# tqfp-sandwich-rf.net
KiCad netlist of a schematic drawn in EAGLE
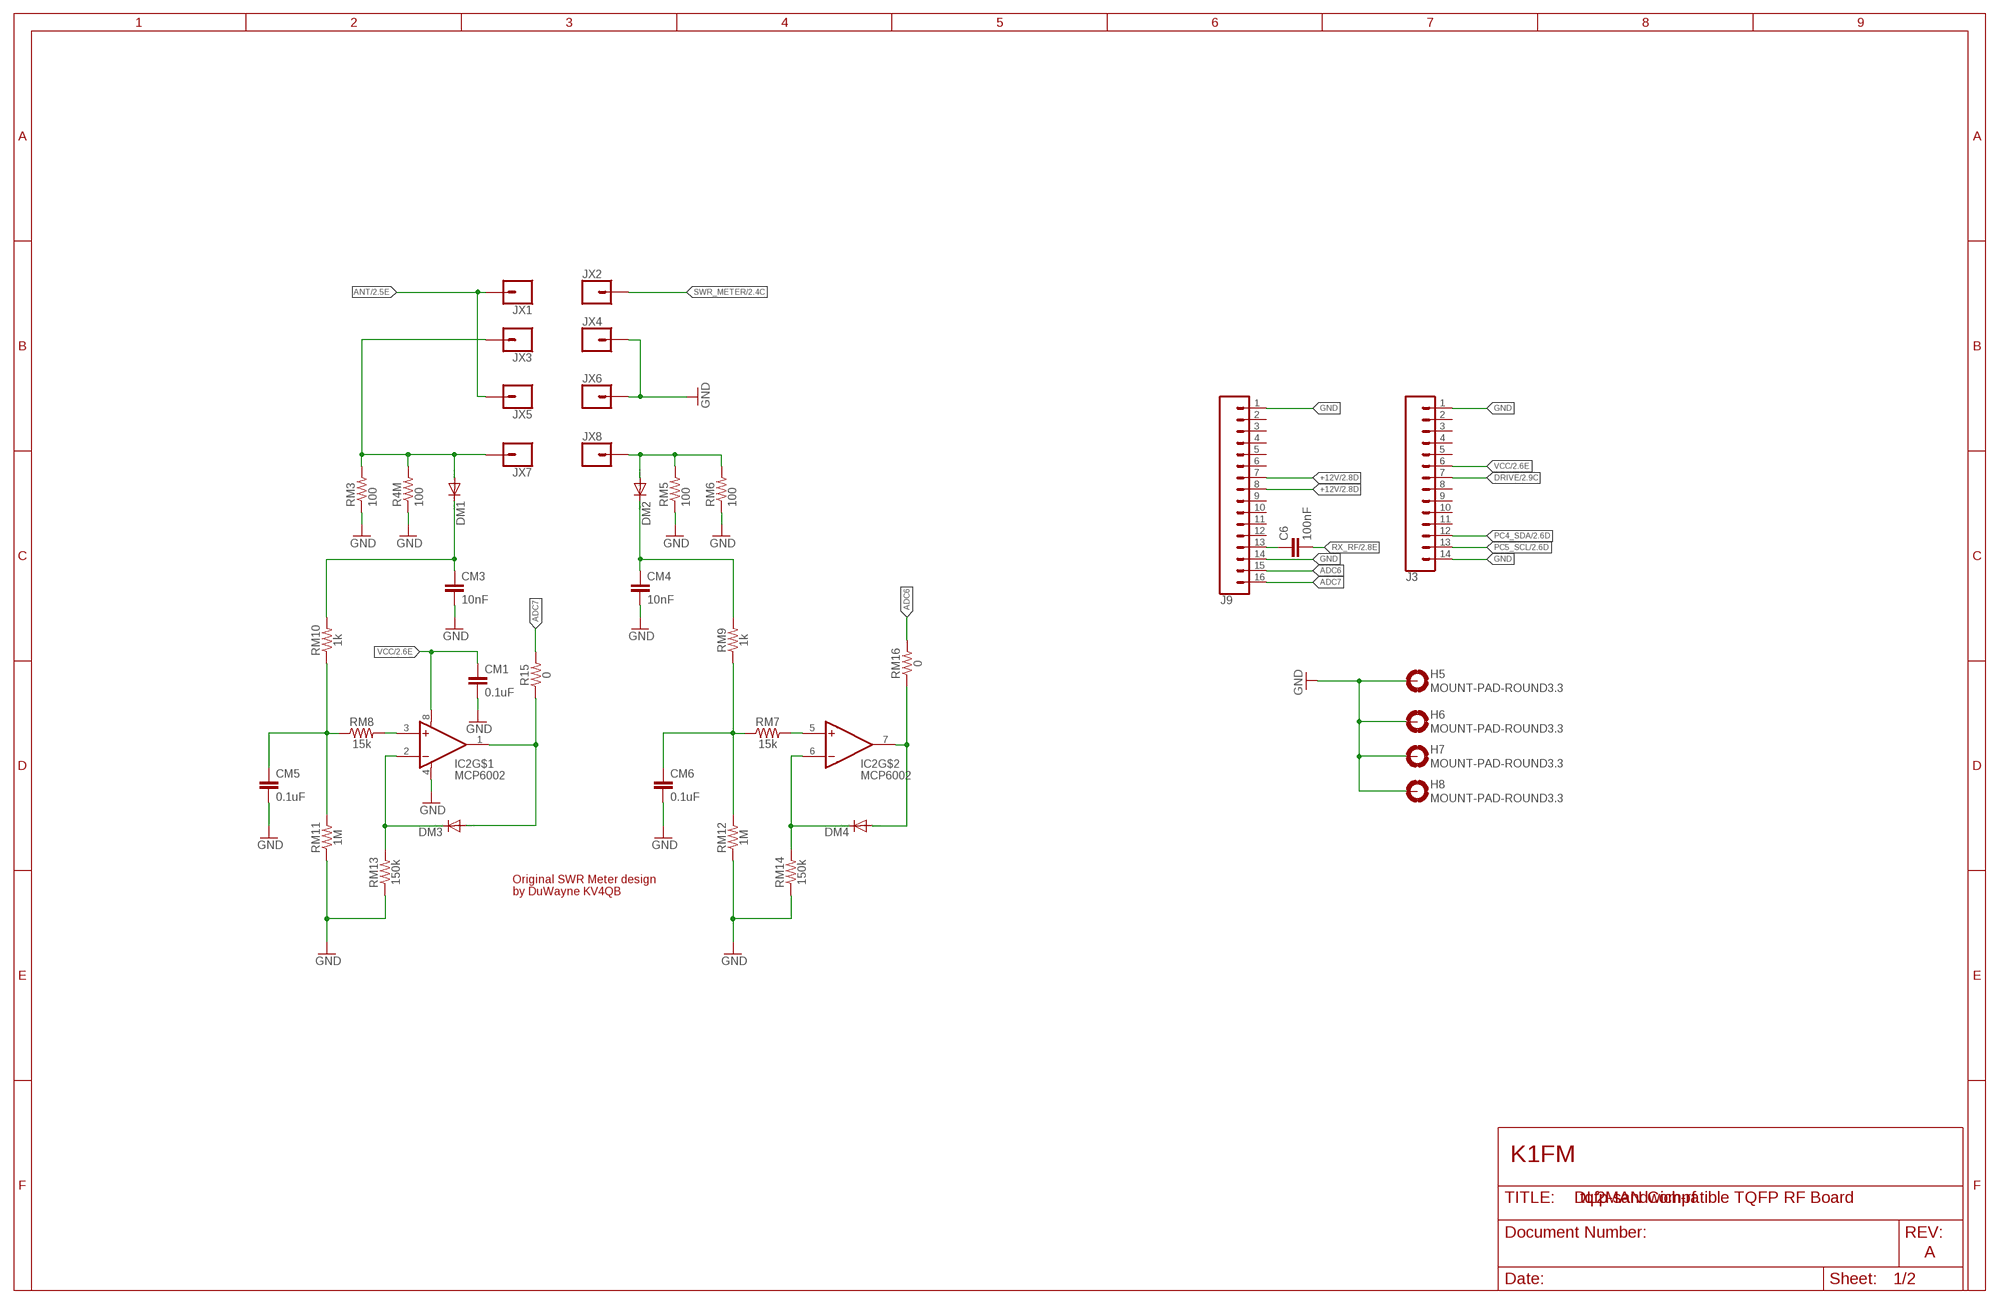
[diagram p0: schematic, sheet 1]
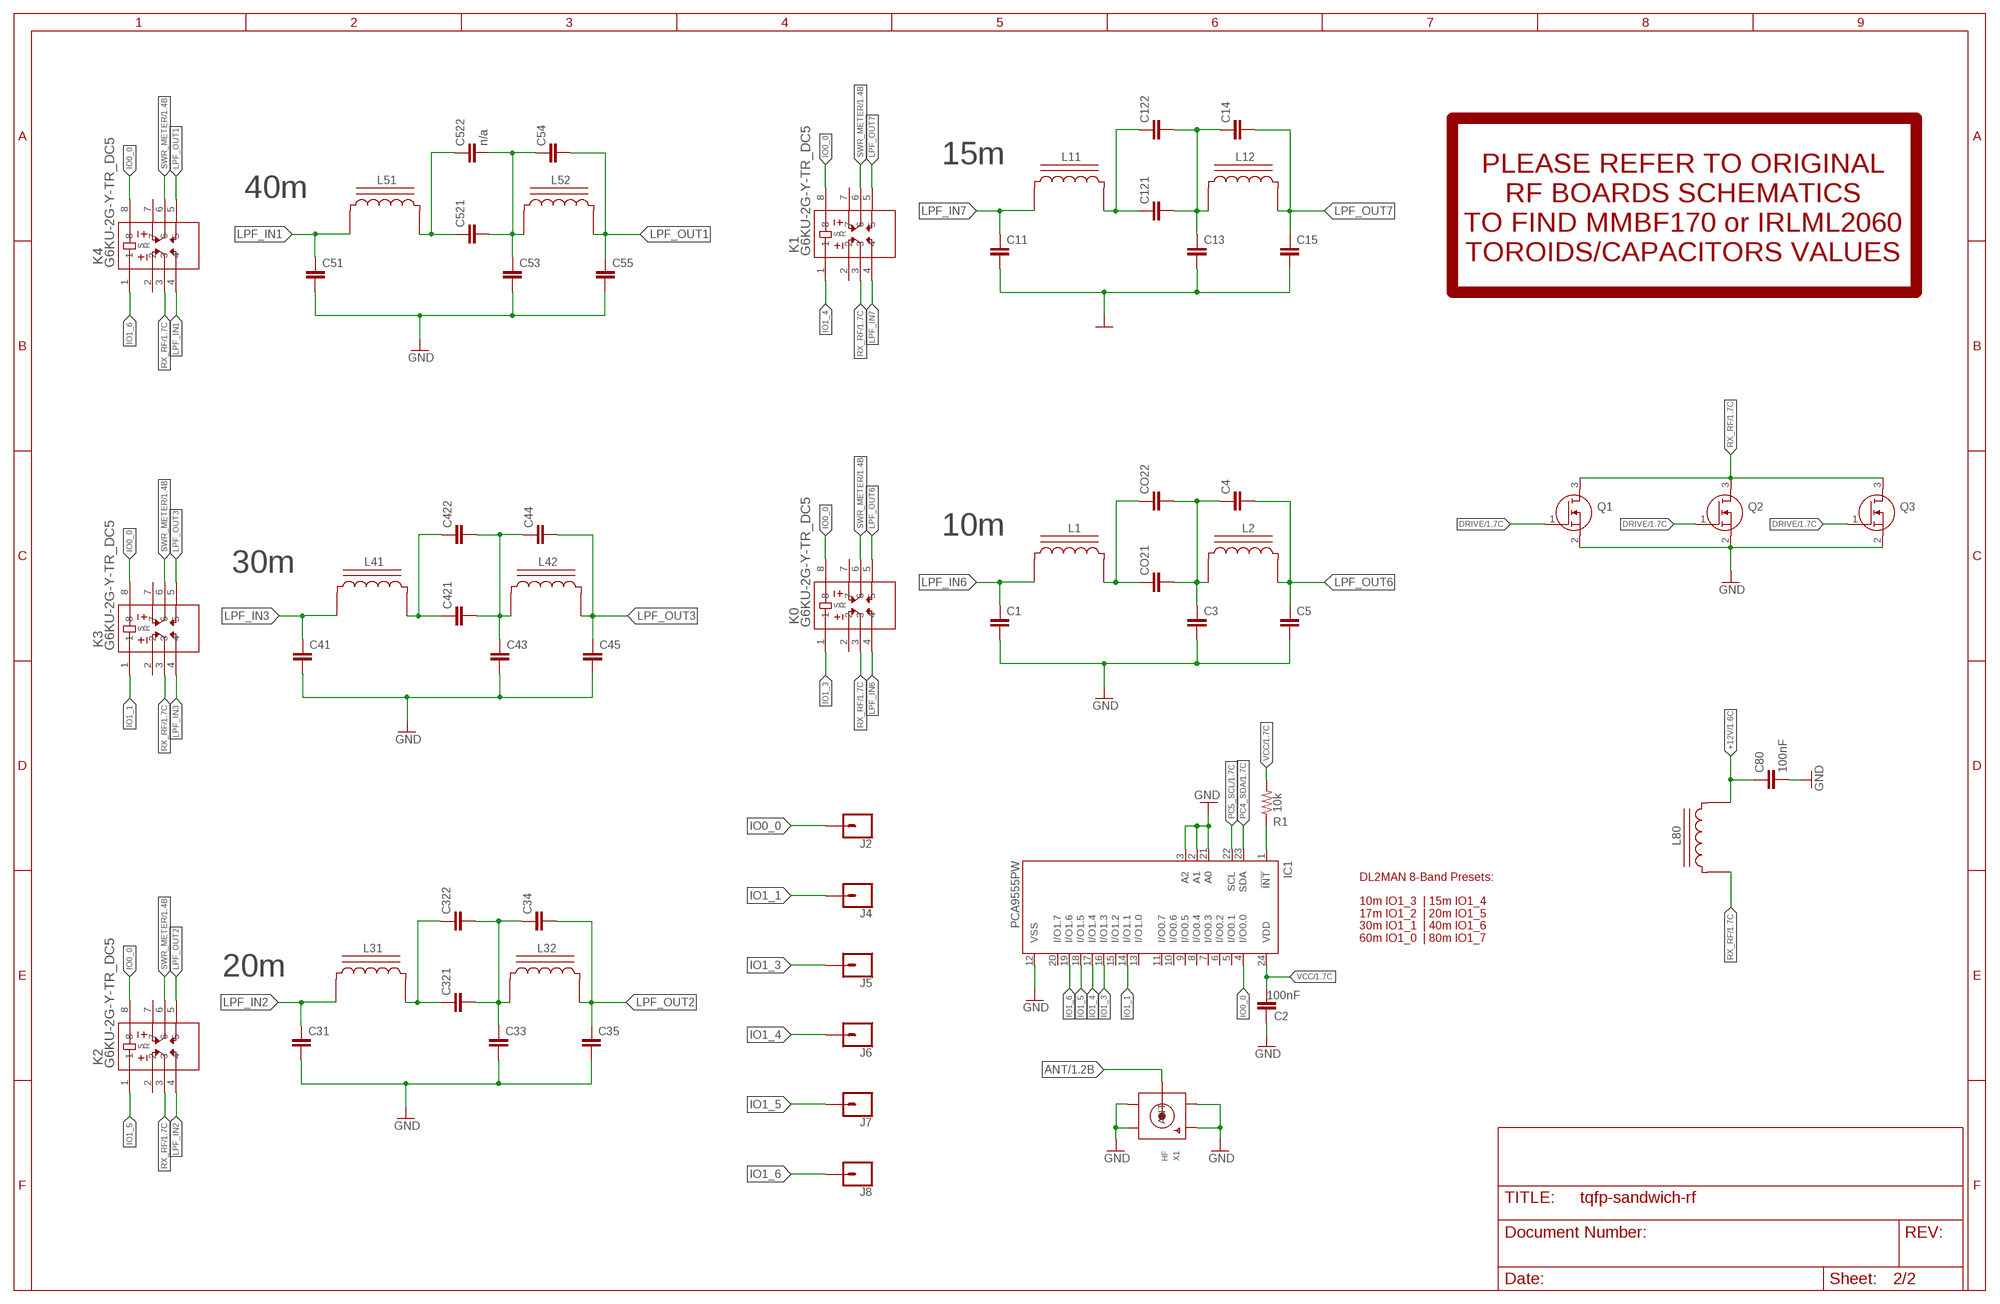
[diagram p1: schematic, sheet 2]

(export (version "E")
  (design (tool "Eeschema 10.0.6"))
  (components
    (comp (ref "C1")
      (value "82pF")
      (footprint "eagle-import:RESC0805_L")
      (libsource (lib "eagle-import") (part "CAPACITOR_0805_L"))
    )
    (comp (ref "C2")
      (value "100nF")
      (footprint "eagle-import:RESC0805_L")
      (libsource (lib "eagle-import") (part "CAPACITOR_0805_L"))
    )
    (comp (ref "C3")
      (value "240pF")
      (footprint "eagle-import:RESC0805_L")
      (libsource (lib "eagle-import") (part "CAPACITOR_0805_L"))
    )
    (comp (ref "C4")
      (value "82pF")
      (footprint "eagle-import:RESC0805_L")
      (libsource (lib "eagle-import") (part "CAPACITOR_0805_L"))
    )
    (comp (ref "C5")
      (value "220pF")
      (footprint "eagle-import:RESC0805_L")
      (libsource (lib "eagle-import") (part "CAPACITOR_0805_L"))
    )
    (comp (ref "C11")
      (value "100pF")
      (footprint "eagle-import:RESC0805_L")
      (libsource (lib "eagle-import") (part "CAPACITOR_0805_L"))
    )
    (comp (ref "C13")
      (value "330pF")
      (footprint "eagle-import:RESC0805_L")
      (libsource (lib "eagle-import") (part "CAPACITOR_0805_L"))
    )
    (comp (ref "C14")
      (value "100pF")
      (footprint "eagle-import:RESC0805_L")
      (libsource (lib "eagle-import") (part "CAPACITOR_0805_L"))
    )
    (comp (ref "C15")
      (value "300pF")
      (footprint "eagle-import:RESC0805_L")
      (libsource (lib "eagle-import") (part "CAPACITOR_0805_L"))
    )
    (comp (ref "C31")
      (value "180pF")
      (footprint "eagle-import:RESC0805_L")
      (libsource (lib "eagle-import") (part "CAPACITOR_0805_L"))
    )
    (comp (ref "C33")
      (value "470pF")
      (footprint "eagle-import:RESC0805_L")
      (libsource (lib "eagle-import") (part "CAPACITOR_0805_L"))
    )
    (comp (ref "C34")
      (value "150pF")
      (footprint "eagle-import:RESC0805_L")
      (libsource (lib "eagle-import") (part "CAPACITOR_0805_L"))
    )
    (comp (ref "C35")
      (value "430pF")
      (footprint "eagle-import:RESC0805_L")
      (libsource (lib "eagle-import") (part "CAPACITOR_0805_L"))
    )
    (comp (ref "C41")
      (value "220pF")
      (footprint "eagle-import:RESC0805_L")
      (libsource (lib "eagle-import") (part "CAPACITOR_0805_L"))
    )
    (comp (ref "C43")
      (value "680pF")
      (footprint "eagle-import:RESC0805_L")
      (libsource (lib "eagle-import") (part "CAPACITOR_0805_L"))
    )
    (comp (ref "C44")
      (value "220pF")
      (footprint "eagle-import:RESC0805_L")
      (libsource (lib "eagle-import") (part "CAPACITOR_0805_L"))
    )
    (comp (ref "C45")
      (value "620pF")
      (footprint "eagle-import:RESC0805_L")
      (libsource (lib "eagle-import") (part "CAPACITOR_0805_L"))
    )
    (comp (ref "C51")
      (value "360pF")
      (footprint "eagle-import:RESC0805_L")
      (libsource (lib "eagle-import") (part "CAPACITOR_0805_L"))
    )
    (comp (ref "C53")
      (value "620pF+330pF")
      (footprint "eagle-import:RESC0805_L")
      (libsource (lib "eagle-import") (part "CAPACITOR_0805_L"))
    )
    (comp (ref "C54")
      (value "330pF")
      (footprint "eagle-import:RESC0805_L")
      (libsource (lib "eagle-import") (part "CAPACITOR_0805_L"))
    )
    (comp (ref "C55")
      (value "470pF+430pF")
      (footprint "eagle-import:RESC0805_L")
      (libsource (lib "eagle-import") (part "CAPACITOR_0805_L"))
    )
    (comp (ref "C80")
      (value "100nF")
      (footprint "eagle-import:RESC0805_L")
      (libsource (lib "eagle-import") (part "CAPACITOR_0805_L"))
    )
    (comp (ref "C121")
      (value "15pF")
      (footprint "eagle-import:RESC0805_L")
      (libsource (lib "eagle-import") (part "CAPACITOR_0805_L"))
    )
    (comp (ref "C122")
      (value "330pF")
      (footprint "eagle-import:RESC0805_L")
      (libsource (lib "eagle-import") (part "CAPACITOR_0805_L"))
    )
    (comp (ref "C321")
      (value "220pF")
      (footprint "eagle-import:RESC0805_L")
      (libsource (lib "eagle-import") (part "CAPACITOR_0805_L"))
    )
    (comp (ref "C322")
      (value "300pF")
      (footprint "eagle-import:RESC0805_L")
      (libsource (lib "eagle-import") (part "CAPACITOR_0805_L"))
    )
    (comp (ref "C421")
      (value "100pF")
      (footprint "eagle-import:RESC0805_L")
      (libsource (lib "eagle-import") (part "CAPACITOR_0805_L"))
    )
    (comp (ref "C422")
      (value "620pF")
      (footprint "eagle-import:RESC0805_L")
      (libsource (lib "eagle-import") (part "CAPACITOR_0805_L"))
    )
    (comp (ref "C521")
      (value "1000pF")
      (footprint "eagle-import:RESC0805_L")
      (libsource (lib "eagle-import") (part "CAPACITOR_0805_L"))
    )
    (comp (ref "C522")
      (value "n/a")
      (footprint "eagle-import:RESC0805_L")
      (libsource (lib "eagle-import") (part "CAPACITOR_0805_L"))
    )
    (comp (ref "CO21")
      (value "56pF")
      (footprint "eagle-import:RESC0805_L")
      (libsource (lib "eagle-import") (part "CAPACITOR_0805_L"))
    )
    (comp (ref "CO22")
      (value "200pF")
      (footprint "eagle-import:RESC0805_L")
      (libsource (lib "eagle-import") (part "CAPACITOR_0805_L"))
    )
    (comp (ref "IC1")
      (value "PCA9555PW")
      (footprint "eagle-import:TSSOP24")
      (libsource (lib "eagle-import") (part "PCA9555PW"))
    )
    (comp (ref "J2")
      (value "CONN_01OFFSET")
      (footprint "eagle-import:1X01_OFFSET")
      (libsource (lib "eagle-import") (part "CONN_01OFFSET"))
    )
    (comp (ref "J4")
      (value "CONN_01OFFSET")
      (footprint "eagle-import:1X01_OFFSET")
      (libsource (lib "eagle-import") (part "CONN_01OFFSET"))
    )
    (comp (ref "J5")
      (value "CONN_01OFFSET")
      (footprint "eagle-import:1X01_OFFSET")
      (libsource (lib "eagle-import") (part "CONN_01OFFSET"))
    )
    (comp (ref "J6")
      (value "CONN_01OFFSET")
      (footprint "eagle-import:1X01_OFFSET")
      (libsource (lib "eagle-import") (part "CONN_01OFFSET"))
    )
    (comp (ref "J7")
      (value "CONN_01OFFSET")
      (footprint "eagle-import:1X01_OFFSET")
      (libsource (lib "eagle-import") (part "CONN_01OFFSET"))
    )
    (comp (ref "J8")
      (value "CONN_01OFFSET")
      (footprint "eagle-import:1X01_OFFSET")
      (libsource (lib "eagle-import") (part "CONN_01OFFSET"))
    )
    (comp (ref "K0")
      (value "G6KU-2G-Y-TR_DC5")
      (footprint "eagle-import:G6KU-2G-Y_DC3_OMR")
      (fields
        (field (name "MANUFACTURER_PART_NUMBER") "G6KU-2G-Y-TR DC5")
        (field (name "COPYRIGHT") "Copyright (C) 2018 Accelerated Designs. All rights reserved")
      )
      (libsource (lib "eagle-import") (part "G6KU-2G-Y-TR_DC5"))
    )
    (comp (ref "K1")
      (value "G6KU-2G-Y-TR_DC5")
      (footprint "eagle-import:G6KU-2G-Y_DC3_OMR")
      (fields
        (field (name "MANUFACTURER_PART_NUMBER") "G6KU-2G-Y-TR DC5")
        (field (name "COPYRIGHT") "Copyright (C) 2018 Accelerated Designs. All rights reserved")
      )
      (libsource (lib "eagle-import") (part "G6KU-2G-Y-TR_DC5"))
    )
    (comp (ref "K2")
      (value "G6KU-2G-Y-TR_DC5")
      (footprint "eagle-import:G6KU-2G-Y_DC3_OMR")
      (fields
        (field (name "MANUFACTURER_PART_NUMBER") "G6KU-2G-Y-TR DC5")
        (field (name "COPYRIGHT") "Copyright (C) 2018 Accelerated Designs. All rights reserved")
      )
      (libsource (lib "eagle-import") (part "G6KU-2G-Y-TR_DC5"))
    )
    (comp (ref "K3")
      (value "G6KU-2G-Y-TR_DC5")
      (footprint "eagle-import:G6KU-2G-Y_DC3_OMR")
      (fields
        (field (name "MANUFACTURER_PART_NUMBER") "G6KU-2G-Y-TR DC5")
        (field (name "COPYRIGHT") "Copyright (C) 2018 Accelerated Designs. All rights reserved")
      )
      (libsource (lib "eagle-import") (part "G6KU-2G-Y-TR_DC5"))
    )
    (comp (ref "K4")
      (value "G6KU-2G-Y-TR_DC5")
      (footprint "eagle-import:G6KU-2G-Y_DC3_OMR")
      (fields
        (field (name "MANUFACTURER_PART_NUMBER") "G6KU-2G-Y-TR DC5")
        (field (name "COPYRIGHT") "Copyright (C) 2018 Accelerated Designs. All rights reserved")
      )
      (libsource (lib "eagle-import") (part "G6KU-2G-Y-TR_DC5"))
    )
    (comp (ref "L1")
      (value "8T/T37-6")
      (footprint "eagle-import:T37_INDUCTOR")
      (libsource (lib "eagle-import") (part "T37_INDUCTOR"))
    )
    (comp (ref "L2")
      (value "5T/T37-6")
      (footprint "eagle-import:T37_INDUCTOR")
      (libsource (lib "eagle-import") (part "T37_INDUCTOR"))
    )
    (comp (ref "L11")
      (value "9T/T37-6")
      (footprint "eagle-import:T37_INDUCTOR")
      (libsource (lib "eagle-import") (part "T37_INDUCTOR"))
    )
    (comp (ref "L12")
      (value "6T/T37-6")
      (footprint "eagle-import:T37_INDUCTOR")
      (libsource (lib "eagle-import") (part "T37_INDUCTOR"))
    )
    (comp (ref "L31")
      (value "12T/T37-6")
      (footprint "eagle-import:T37_INDUCTOR")
      (libsource (lib "eagle-import") (part "T37_INDUCTOR"))
    )
    (comp (ref "L32")
      (value "8T/T37-2")
      (footprint "eagle-import:T37_INDUCTOR")
      (libsource (lib "eagle-import") (part "T37_INDUCTOR"))
    )
    (comp (ref "L41")
      (value "12T/T37-2")
      (footprint "eagle-import:T37_INDUCTOR")
      (libsource (lib "eagle-import") (part "T37_INDUCTOR"))
    )
    (comp (ref "L42")
      (value "8T/T37-2")
      (footprint "eagle-import:T37_INDUCTOR")
      (libsource (lib "eagle-import") (part "T37_INDUCTOR"))
    )
    (comp (ref "L51")
      (value "15T/T37-2")
      (footprint "eagle-import:T37_INDUCTOR")
      (libsource (lib "eagle-import") (part "T37_INDUCTOR"))
    )
    (comp (ref "L52")
      (value "9T/T37-2")
      (footprint "eagle-import:T37_INDUCTOR")
      (libsource (lib "eagle-import") (part "T37_INDUCTOR"))
    )
    (comp (ref "L80")
      (value "12T/FT37-43")
      (footprint "eagle-import:T37_INDUCTOR")
      (libsource (lib "eagle-import") (part "T37_INDUCTOR"))
    )
    (comp (ref "Q1")
      (value "MMBF170")
      (footprint "eagle-import:SOT96P237X111-3N")
      (fields (field (name "MOUSER_PART_NUMBER") "512-MMBF170"))
      (libsource (lib "eagle-import") (part "MMBF170"))
    )
    (comp (ref "Q2")
      (value "MMBF170")
      (footprint "eagle-import:SOT96P237X111-3N")
      (fields (field (name "MOUSER_PART_NUMBER") "512-MMBF170"))
      (libsource (lib "eagle-import") (part "MMBF170"))
    )
    (comp (ref "Q3")
      (value "MMBF170")
      (footprint "eagle-import:SOT96P237X111-3N")
      (fields (field (name "MOUSER_PART_NUMBER") "512-MMBF170"))
      (libsource (lib "eagle-import") (part "MMBF170"))
    )
    (comp (ref "R1")
      (value "10k")
      (footprint "eagle-import:0603")
      (libsource (lib "eagle-import") (part "10KOHM-0603-1/10W-1%"))
    )
    (comp (ref "X1")
      (value "HF")
      (footprint "eagle-import:SMA_EDGELAUNCH")
      (libsource (lib "eagle-import") (part "SMACONNECTOR_EDGE"))
    )
    (comp (ref "C6")
      (value "100nF")
      (footprint "eagle-import:RESC0805_L")
      (libsource (lib "eagle-import") (part "CAPACITOR_0805_L"))
    )
    (comp (ref "CM1")
      (value "0.1uF")
      (footprint "eagle-import:0603")
      (libsource (lib "eagle-import") (part "0.1UF-0603-100V-10%"))
    )
    (comp (ref "CM3")
      (value "10nF")
      (footprint "eagle-import:0603")
      (libsource (lib "eagle-import") (part "10NF-0603-50V-10%"))
    )
    (comp (ref "CM4")
      (value "10nF")
      (footprint "eagle-import:0603")
      (libsource (lib "eagle-import") (part "10NF-0603-50V-10%"))
    )
    (comp (ref "CM5")
      (value "0.1uF")
      (footprint "eagle-import:0603")
      (libsource (lib "eagle-import") (part "0.1UF-0603-100V-10%"))
    )
    (comp (ref "CM6")
      (value "0.1uF")
      (footprint "eagle-import:0603")
      (libsource (lib "eagle-import") (part "0.1UF-0603-100V-10%"))
    )
    (comp (ref "DM1")
      (value "1N60P")
      (footprint "eagle-import:DO35-10")
      (libsource (lib "eagle-import") (part "1N4148DO35-10"))
    )
    (comp (ref "DM2")
      (value "1N60P")
      (footprint "eagle-import:DO35-10")
      (libsource (lib "eagle-import") (part "1N4148DO35-10"))
    )
    (comp (ref "DM3")
      (value "1N60P")
      (footprint "eagle-import:DO35-10")
      (libsource (lib "eagle-import") (part "1N4148DO35-10"))
    )
    (comp (ref "DM4")
      (value "1N60P")
      (footprint "eagle-import:DO35-10")
      (libsource (lib "eagle-import") (part "1N4148DO35-10"))
    )
    (comp (ref "H5")
      (value "MOUNT-PAD-ROUND3.3")
      (footprint "eagle-import:3,3-PAD")
      (libsource (lib "eagle-import") (part "MOUNT-PAD-ROUND3.3"))
    )
    (comp (ref "H6")
      (value "MOUNT-PAD-ROUND3.3")
      (footprint "eagle-import:3,3-PAD")
      (libsource (lib "eagle-import") (part "MOUNT-PAD-ROUND3.3"))
    )
    (comp (ref "H7")
      (value "MOUNT-PAD-ROUND3.3")
      (footprint "eagle-import:3,3-PAD")
      (libsource (lib "eagle-import") (part "MOUNT-PAD-ROUND3.3"))
    )
    (comp (ref "H8")
      (value "MOUNT-PAD-ROUND3.3")
      (footprint "eagle-import:3,3-PAD")
      (libsource (lib "eagle-import") (part "MOUNT-PAD-ROUND3.3"))
    )
    (comp (ref "IC2")
      (value "MCP6002")
      (footprint "eagle-import:SOIC8")
      (libsource (lib "eagle-import") (part "MCP6293"))
    )
    (comp (ref "J3")
      (value "CONN_14")
      (footprint "eagle-import:1X14")
      (libsource (lib "eagle-import") (part "CONN_14"))
    )
    (comp (ref "J9")
      (value "CONN_16")
      (footprint "eagle-import:1X16")
      (libsource (lib "eagle-import") (part "CONN_16"))
    )
    (comp (ref "JX1")
      (value "CONN_01")
      (footprint "eagle-import:1X01")
      (libsource (lib "eagle-import") (part "CONN_01"))
    )
    (comp (ref "JX2")
      (value "CONN_01")
      (footprint "eagle-import:1X01")
      (libsource (lib "eagle-import") (part "CONN_01"))
    )
    (comp (ref "JX3")
      (value "CONN_01")
      (footprint "eagle-import:1X01")
      (libsource (lib "eagle-import") (part "CONN_01"))
    )
    (comp (ref "JX4")
      (value "CONN_01")
      (footprint "eagle-import:1X01")
      (libsource (lib "eagle-import") (part "CONN_01"))
    )
    (comp (ref "JX5")
      (value "CONN_01")
      (footprint "eagle-import:1X01")
      (libsource (lib "eagle-import") (part "CONN_01"))
    )
    (comp (ref "JX6")
      (value "CONN_01")
      (footprint "eagle-import:1X01")
      (libsource (lib "eagle-import") (part "CONN_01"))
    )
    (comp (ref "JX7")
      (value "CONN_01")
      (footprint "eagle-import:1X01")
      (libsource (lib "eagle-import") (part "CONN_01"))
    )
    (comp (ref "JX8")
      (value "CONN_01")
      (footprint "eagle-import:1X01")
      (libsource (lib "eagle-import") (part "CONN_01"))
    )
    (comp (ref "R4M")
      (value "100")
      (footprint "eagle-import:M1206")
      (libsource (lib "eagle-import") (part "R-US_M1206"))
    )
    (comp (ref "R15")
      (value "0")
      (footprint "eagle-import:0603")
      (libsource (lib "eagle-import") (part "1KOHM-0603-1/10W-1%"))
    )
    (comp (ref "RM3")
      (value "100")
      (footprint "eagle-import:M1206")
      (libsource (lib "eagle-import") (part "R-US_M1206"))
    )
    (comp (ref "RM5")
      (value "100")
      (footprint "eagle-import:M1206")
      (libsource (lib "eagle-import") (part "R-US_M1206"))
    )
    (comp (ref "RM6")
      (value "100")
      (footprint "eagle-import:M1206")
      (libsource (lib "eagle-import") (part "R-US_M1206"))
    )
    (comp (ref "RM7")
      (value "15k")
      (footprint "eagle-import:0603")
      (libsource (lib "eagle-import") (part "15KOHM-0603-1/10W-1%"))
    )
    (comp (ref "RM8")
      (value "15k")
      (footprint "eagle-import:0603")
      (libsource (lib "eagle-import") (part "15KOHM-0603-1/10W-1%"))
    )
    (comp (ref "RM9")
      (value "1k")
      (footprint "eagle-import:0603")
      (libsource (lib "eagle-import") (part "1KOHM-0603-1/10W-1%"))
    )
    (comp (ref "RM10")
      (value "1k")
      (footprint "eagle-import:0603")
      (libsource (lib "eagle-import") (part "1KOHM-0603-1/10W-1%"))
    )
    (comp (ref "RM11")
      (value "1M")
      (footprint "eagle-import:0603")
      (libsource (lib "eagle-import") (part "1MOHM-0603-1/4W-5%"))
    )
    (comp (ref "RM12")
      (value "1M")
      (footprint "eagle-import:0603")
      (libsource (lib "eagle-import") (part "1MOHM-0603-1/4W-5%"))
    )
    (comp (ref "RM13")
      (value "150k")
      (footprint "eagle-import:0603")
      (libsource (lib "eagle-import") (part "150KOHM-0603-1/10W-1%"))
    )
    (comp (ref "RM14")
      (value "150k")
      (footprint "eagle-import:0603")
      (libsource (lib "eagle-import") (part "150KOHM-0603-1/10W-1%"))
    )
    (comp (ref "RM16")
      (value "0")
      (footprint "eagle-import:0603")
      (libsource (lib "eagle-import") (part "1KOHM-0603-1/10W-1%"))
    )
  )
  (nets
    (net (code "1") (name "+12V") (class "Default")
      (node (ref "C80") (pin "1") (pinfunction "1_1") (pintype "passive"))
      (node (ref "J9") (pin "7") (pinfunction "7_7") (pintype "passive"))
      (node (ref "J9") (pin "8") (pinfunction "8_8") (pintype "passive"))
      (node (ref "L80") (pin "CA") (pinfunction "CA_CA") (pintype "bidirectional"))
    )
    (net (code "2") (name "ADC6") (class "Default")
      (node (ref "J9") (pin "15") (pinfunction "15_15") (pintype "passive"))
      (node (ref "RM16") (pin "2") (pinfunction "2_2") (pintype "passive"))
    )
    (net (code "3") (name "ADC7") (class "Default")
      (node (ref "J9") (pin "16") (pinfunction "16_16") (pintype "passive"))
      (node (ref "R15") (pin "2") (pinfunction "2_2") (pintype "passive"))
    )
    (net (code "4") (name "ANT") (class "Default")
      (node (ref "JX1") (pin "1") (pinfunction "1_1") (pintype "passive"))
      (node (ref "JX5") (pin "1") (pinfunction "1_1") (pintype "passive"))
      (node (ref "X1") (pin "P") (pinfunction "ANT_P") (pintype "bidirectional"))
    )
    (net (code "5") (name "DRIVE") (class "Default")
      (node (ref "J3") (pin "7") (pinfunction "7_7") (pintype "passive"))
      (node (ref "Q1") (pin "1") (pinfunction "G_1") (pintype "bidirectional"))
      (node (ref "Q2") (pin "1") (pinfunction "G_1") (pintype "bidirectional"))
      (node (ref "Q3") (pin "1") (pinfunction "G_1") (pintype "bidirectional"))
    )
    (net (code "6") (name "GND") (class "Default")
      (node (ref "C1") (pin "2") (pinfunction "2_2") (pintype "passive"))
      (node (ref "C11") (pin "2") (pinfunction "2_2") (pintype "passive"))
      (node (ref "C13") (pin "2") (pinfunction "2_2") (pintype "passive"))
      (node (ref "C15") (pin "2") (pinfunction "2_2") (pintype "passive"))
      (node (ref "C2") (pin "1") (pinfunction "1_1") (pintype "passive"))
      (node (ref "C3") (pin "2") (pinfunction "2_2") (pintype "passive"))
      (node (ref "C31") (pin "2") (pinfunction "2_2") (pintype "passive"))
      (node (ref "C33") (pin "2") (pinfunction "2_2") (pintype "passive"))
      (node (ref "C35") (pin "2") (pinfunction "2_2") (pintype "passive"))
      (node (ref "C41") (pin "2") (pinfunction "2_2") (pintype "passive"))
      (node (ref "C43") (pin "2") (pinfunction "2_2") (pintype "passive"))
      (node (ref "C45") (pin "2") (pinfunction "2_2") (pintype "passive"))
      (node (ref "C5") (pin "2") (pinfunction "2_2") (pintype "passive"))
      (node (ref "C51") (pin "2") (pinfunction "2_2") (pintype "passive"))
      (node (ref "C53") (pin "2") (pinfunction "2_2") (pintype "passive"))
      (node (ref "C55") (pin "2") (pinfunction "2_2") (pintype "passive"))
      (node (ref "C80") (pin "2") (pinfunction "2_2") (pintype "passive"))
      (node (ref "CM1") (pin "2") (pinfunction "2_2") (pintype "passive"))
      (node (ref "CM3") (pin "2") (pinfunction "2_2") (pintype "passive"))
      (node (ref "CM4") (pin "2") (pinfunction "2_2") (pintype "passive"))
      (node (ref "CM5") (pin "2") (pinfunction "2_2") (pintype "passive"))
      (node (ref "CM6") (pin "2") (pinfunction "2_2") (pintype "passive"))
      (node (ref "H5") (pin "B3,3") (pinfunction "MOUNT_B3,3") (pintype "passive"))
      (node (ref "H6") (pin "B3,3") (pinfunction "MOUNT_B3,3") (pintype "passive"))
      (node (ref "H7") (pin "B3,3") (pinfunction "MOUNT_B3,3") (pintype "passive"))
      (node (ref "H8") (pin "B3,3") (pinfunction "MOUNT_B3,3") (pintype "passive"))
      (node (ref "IC1") (pin "12") (pinfunction "VSS_12") (pintype "power_in"))
      (node (ref "IC1") (pin "2") (pinfunction "A1_2") (pintype "input"))
      (node (ref "IC1") (pin "21") (pinfunction "A0_21") (pintype "input"))
      (node (ref "IC1") (pin "3") (pinfunction "A2_3") (pintype "input"))
      (node (ref "IC2") (pin "4") (pinfunction "V-_4") (pintype "power_in"))
      (node (ref "J3") (pin "1") (pinfunction "1_1") (pintype "passive"))
      (node (ref "J3") (pin "14") (pinfunction "14_14") (pintype "passive"))
      (node (ref "J9") (pin "1") (pinfunction "1_1") (pintype "passive"))
      (node (ref "J9") (pin "14") (pinfunction "14_14") (pintype "passive"))
      (node (ref "JX4") (pin "1") (pinfunction "1_1") (pintype "passive"))
      (node (ref "JX6") (pin "1") (pinfunction "1_1") (pintype "passive"))
      (node (ref "Q1") (pin "2") (pinfunction "S_2") (pintype "bidirectional"))
      (node (ref "Q2") (pin "2") (pinfunction "S_2") (pintype "bidirectional"))
      (node (ref "Q3") (pin "2") (pinfunction "S_2") (pintype "bidirectional"))
      (node (ref "R4M") (pin "1") (pinfunction "1_1") (pintype "passive"))
      (node (ref "RM11") (pin "1") (pinfunction "1_1") (pintype "passive"))
      (node (ref "RM12") (pin "1") (pinfunction "1_1") (pintype "passive"))
      (node (ref "RM13") (pin "1") (pinfunction "1_1") (pintype "passive"))
      (node (ref "RM14") (pin "1") (pinfunction "1_1") (pintype "passive"))
      (node (ref "RM3") (pin "1") (pinfunction "1_1") (pintype "passive"))
      (node (ref "RM5") (pin "1") (pinfunction "1_1") (pintype "passive"))
      (node (ref "RM6") (pin "1") (pinfunction "1_1") (pintype "passive"))
      (node (ref "X1") (pin "GND@1") (pinfunction "GND4_GND@1") (pintype "power_in"))
      (node (ref "X1") (pin "GND@2") (pinfunction "GND3_GND@2") (pintype "power_in"))
      (node (ref "X1") (pin "GND@3") (pinfunction "GND2_GND@3") (pintype "power_in"))
      (node (ref "X1") (pin "GND@4") (pinfunction "GND1_GND@4") (pintype "power_in"))
    )
    (net (code "7") (name "IO0_0") (class "Default")
      (node (ref "IC1") (pin "4") (pinfunction "I/O0.0_4") (pintype "bidirectional"))
      (node (ref "J2") (pin "1") (pinfunction "1_1") (pintype "passive"))
      (node (ref "K0") (pin "8") (pinfunction "8_8") (pintype "passive"))
      (node (ref "K1") (pin "8") (pinfunction "8_8") (pintype "passive"))
      (node (ref "K2") (pin "8") (pinfunction "8_8") (pintype "passive"))
      (node (ref "K3") (pin "8") (pinfunction "8_8") (pintype "passive"))
      (node (ref "K4") (pin "8") (pinfunction "8_8") (pintype "passive"))
    )
    (net (code "8") (name "IO1_1") (class "Default")
      (node (ref "IC1") (pin "14") (pinfunction "I/O1.1_14") (pintype "bidirectional"))
      (node (ref "J4") (pin "1") (pinfunction "1_1") (pintype "passive"))
      (node (ref "K3") (pin "1") (pinfunction "1_1") (pintype "passive"))
    )
    (net (code "9") (name "IO1_3") (class "Default")
      (node (ref "IC1") (pin "16") (pinfunction "I/O1.3_16") (pintype "bidirectional"))
      (node (ref "J5") (pin "1") (pinfunction "1_1") (pintype "passive"))
      (node (ref "K0") (pin "1") (pinfunction "1_1") (pintype "passive"))
    )
    (net (code "10") (name "IO1_4") (class "Default")
      (node (ref "IC1") (pin "17") (pinfunction "I/O1.4_17") (pintype "bidirectional"))
      (node (ref "J6") (pin "1") (pinfunction "1_1") (pintype "passive"))
      (node (ref "K1") (pin "1") (pinfunction "1_1") (pintype "passive"))
    )
    (net (code "11") (name "IO1_5") (class "Default")
      (node (ref "IC1") (pin "18") (pinfunction "I/O1.5_18") (pintype "bidirectional"))
      (node (ref "J7") (pin "1") (pinfunction "1_1") (pintype "passive"))
      (node (ref "K2") (pin "1") (pinfunction "1_1") (pintype "passive"))
    )
    (net (code "12") (name "IO1_6") (class "Default")
      (node (ref "IC1") (pin "19") (pinfunction "I/O1.6_19") (pintype "bidirectional"))
      (node (ref "J8") (pin "1") (pinfunction "1_1") (pintype "passive"))
      (node (ref "K4") (pin "1") (pinfunction "1_1") (pintype "passive"))
    )
    (net (code "13") (name "LPF_IN1") (class "Default")
      (node (ref "C51") (pin "1") (pinfunction "1_1") (pintype "passive"))
      (node (ref "K4") (pin "4") (pinfunction "4_4") (pintype "passive"))
      (node (ref "L51") (pin "CB") (pinfunction "CB_CB") (pintype "bidirectional"))
    )
    (net (code "14") (name "LPF_IN2") (class "Default")
      (node (ref "C31") (pin "1") (pinfunction "1_1") (pintype "passive"))
      (node (ref "K2") (pin "4") (pinfunction "4_4") (pintype "passive"))
      (node (ref "L31") (pin "CB") (pinfunction "CB_CB") (pintype "bidirectional"))
    )
    (net (code "15") (name "LPF_IN3") (class "Default")
      (node (ref "C41") (pin "1") (pinfunction "1_1") (pintype "passive"))
      (node (ref "K3") (pin "4") (pinfunction "4_4") (pintype "passive"))
      (node (ref "L41") (pin "CB") (pinfunction "CB_CB") (pintype "bidirectional"))
    )
    (net (code "16") (name "LPF_IN6") (class "Default")
      (node (ref "C1") (pin "1") (pinfunction "1_1") (pintype "passive"))
      (node (ref "K0") (pin "4") (pinfunction "4_4") (pintype "passive"))
      (node (ref "L1") (pin "CB") (pinfunction "CB_CB") (pintype "bidirectional"))
    )
    (net (code "17") (name "LPF_IN7") (class "Default")
      (node (ref "C11") (pin "1") (pinfunction "1_1") (pintype "passive"))
      (node (ref "K1") (pin "4") (pinfunction "4_4") (pintype "passive"))
      (node (ref "L11") (pin "CB") (pinfunction "CB_CB") (pintype "bidirectional"))
    )
    (net (code "18") (name "LPF_OUT1") (class "Default")
      (node (ref "C54") (pin "2") (pinfunction "2_2") (pintype "passive"))
      (node (ref "C55") (pin "1") (pinfunction "1_1") (pintype "passive"))
      (node (ref "K4") (pin "5") (pinfunction "5_5") (pintype "passive"))
      (node (ref "L52") (pin "CA") (pinfunction "CA_CA") (pintype "bidirectional"))
    )
    (net (code "19") (name "LPF_OUT2") (class "Default")
      (node (ref "C34") (pin "2") (pinfunction "2_2") (pintype "passive"))
      (node (ref "C35") (pin "1") (pinfunction "1_1") (pintype "passive"))
      (node (ref "K2") (pin "5") (pinfunction "5_5") (pintype "passive"))
      (node (ref "L32") (pin "CA") (pinfunction "CA_CA") (pintype "bidirectional"))
    )
    (net (code "20") (name "LPF_OUT3") (class "Default")
      (node (ref "C44") (pin "2") (pinfunction "2_2") (pintype "passive"))
      (node (ref "C45") (pin "1") (pinfunction "1_1") (pintype "passive"))
      (node (ref "K3") (pin "5") (pinfunction "5_5") (pintype "passive"))
      (node (ref "L42") (pin "CA") (pinfunction "CA_CA") (pintype "bidirectional"))
    )
    (net (code "21") (name "LPF_OUT6") (class "Default")
      (node (ref "C4") (pin "2") (pinfunction "2_2") (pintype "passive"))
      (node (ref "C5") (pin "1") (pinfunction "1_1") (pintype "passive"))
      (node (ref "K0") (pin "5") (pinfunction "5_5") (pintype "passive"))
      (node (ref "L2") (pin "CA") (pinfunction "CA_CA") (pintype "bidirectional"))
    )
    (net (code "22") (name "LPF_OUT7") (class "Default")
      (node (ref "C14") (pin "2") (pinfunction "2_2") (pintype "passive"))
      (node (ref "C15") (pin "1") (pinfunction "1_1") (pintype "passive"))
      (node (ref "K1") (pin "5") (pinfunction "5_5") (pintype "passive"))
      (node (ref "L12") (pin "CA") (pinfunction "CA_CA") (pintype "bidirectional"))
    )
    (net (code "23") (name "Net-(C3-Pad1)") (class "Default")
      (node (ref "C3") (pin "1") (pinfunction "1_1") (pintype "passive"))
      (node (ref "C4") (pin "1") (pinfunction "1_1") (pintype "passive"))
      (node (ref "CO21") (pin "2") (pinfunction "2_2") (pintype "passive"))
      (node (ref "CO22") (pin "2") (pinfunction "2_2") (pintype "passive"))
      (node (ref "L2") (pin "CB") (pinfunction "CB_CB") (pintype "bidirectional"))
    )
    (net (code "24") (name "Net-(C6-Pad1)") (class "Default")
      (node (ref "C6") (pin "1") (pinfunction "1_1") (pintype "passive"))
      (node (ref "J9") (pin "13") (pinfunction "13_13") (pintype "passive"))
    )
    (net (code "25") (name "Net-(C121-Pad1)") (class "Default")
      (node (ref "C121") (pin "1") (pinfunction "1_1") (pintype "passive"))
      (node (ref "C122") (pin "1") (pinfunction "1_1") (pintype "passive"))
      (node (ref "L11") (pin "CA") (pinfunction "CA_CA") (pintype "bidirectional"))
    )
    (net (code "26") (name "Net-(C121-Pad2)") (class "Default")
      (node (ref "C121") (pin "2") (pinfunction "2_2") (pintype "passive"))
      (node (ref "C122") (pin "2") (pinfunction "2_2") (pintype "passive"))
      (node (ref "C13") (pin "1") (pinfunction "1_1") (pintype "passive"))
      (node (ref "C14") (pin "1") (pinfunction "1_1") (pintype "passive"))
      (node (ref "L12") (pin "CB") (pinfunction "CB_CB") (pintype "bidirectional"))
    )
    (net (code "27") (name "Net-(C321-Pad1)") (class "Default")
      (node (ref "C321") (pin "1") (pinfunction "1_1") (pintype "passive"))
      (node (ref "C322") (pin "1") (pinfunction "1_1") (pintype "passive"))
      (node (ref "L31") (pin "CA") (pinfunction "CA_CA") (pintype "bidirectional"))
    )
    (net (code "28") (name "Net-(C321-Pad2)") (class "Default")
      (node (ref "C321") (pin "2") (pinfunction "2_2") (pintype "passive"))
      (node (ref "C322") (pin "2") (pinfunction "2_2") (pintype "passive"))
      (node (ref "C33") (pin "1") (pinfunction "1_1") (pintype "passive"))
      (node (ref "C34") (pin "1") (pinfunction "1_1") (pintype "passive"))
      (node (ref "L32") (pin "CB") (pinfunction "CB_CB") (pintype "bidirectional"))
    )
    (net (code "29") (name "Net-(C421-Pad1)") (class "Default")
      (node (ref "C421") (pin "1") (pinfunction "1_1") (pintype "passive"))
      (node (ref "C422") (pin "1") (pinfunction "1_1") (pintype "passive"))
      (node (ref "L41") (pin "CA") (pinfunction "CA_CA") (pintype "bidirectional"))
    )
    (net (code "30") (name "Net-(C421-Pad2)") (class "Default")
      (node (ref "C421") (pin "2") (pinfunction "2_2") (pintype "passive"))
      (node (ref "C422") (pin "2") (pinfunction "2_2") (pintype "passive"))
      (node (ref "C43") (pin "1") (pinfunction "1_1") (pintype "passive"))
      (node (ref "C44") (pin "1") (pinfunction "1_1") (pintype "passive"))
      (node (ref "L42") (pin "CB") (pinfunction "CB_CB") (pintype "bidirectional"))
    )
    (net (code "31") (name "Net-(C521-Pad1)") (class "Default")
      (node (ref "C521") (pin "1") (pinfunction "1_1") (pintype "passive"))
      (node (ref "C522") (pin "1") (pinfunction "1_1") (pintype "passive"))
      (node (ref "L51") (pin "CA") (pinfunction "CA_CA") (pintype "bidirectional"))
    )
    (net (code "32") (name "Net-(C521-Pad2)") (class "Default")
      (node (ref "C521") (pin "2") (pinfunction "2_2") (pintype "passive"))
      (node (ref "C522") (pin "2") (pinfunction "2_2") (pintype "passive"))
      (node (ref "C53") (pin "1") (pinfunction "1_1") (pintype "passive"))
      (node (ref "C54") (pin "1") (pinfunction "1_1") (pintype "passive"))
      (node (ref "L52") (pin "CB") (pinfunction "CB_CB") (pintype "bidirectional"))
    )
    (net (code "33") (name "Net-(CM3-Pad1)") (class "Default")
      (node (ref "CM3") (pin "1") (pinfunction "1_1") (pintype "passive"))
      (node (ref "DM1") (pin "C") (pinfunction "C_C") (pintype "passive"))
      (node (ref "RM10") (pin "2") (pinfunction "2_2") (pintype "passive"))
    )
    (net (code "34") (name "Net-(CM4-Pad1)") (class "Default")
      (node (ref "CM4") (pin "1") (pinfunction "1_1") (pintype "passive"))
      (node (ref "DM2") (pin "C") (pinfunction "C_C") (pintype "passive"))
      (node (ref "RM9") (pin "2") (pinfunction "2_2") (pintype "passive"))
    )
    (net (code "35") (name "Net-(CM5-Pad1)") (class "Default")
      (node (ref "CM5") (pin "1") (pinfunction "1_1") (pintype "passive"))
      (node (ref "RM10") (pin "1") (pinfunction "1_1") (pintype "passive"))
      (node (ref "RM11") (pin "2") (pinfunction "2_2") (pintype "passive"))
      (node (ref "RM8") (pin "1") (pinfunction "1_1") (pintype "passive"))
    )
    (net (code "36") (name "Net-(CM6-Pad1)") (class "Default")
      (node (ref "CM6") (pin "1") (pinfunction "1_1") (pintype "passive"))
      (node (ref "RM12") (pin "2") (pinfunction "2_2") (pintype "passive"))
      (node (ref "RM7") (pin "1") (pinfunction "1_1") (pintype "passive"))
      (node (ref "RM9") (pin "1") (pinfunction "1_1") (pintype "passive"))
    )
    (net (code "37") (name "Net-(CO21-Pad1)") (class "Default")
      (node (ref "CO21") (pin "1") (pinfunction "1_1") (pintype "passive"))
      (node (ref "CO22") (pin "1") (pinfunction "1_1") (pintype "passive"))
      (node (ref "L1") (pin "CA") (pinfunction "CA_CA") (pintype "bidirectional"))
    )
    (net (code "38") (name "Net-(DM1-PadA)") (class "Default")
      (node (ref "DM1") (pin "A") (pinfunction "A_A") (pintype "passive"))
      (node (ref "JX3") (pin "1") (pinfunction "1_1") (pintype "passive"))
      (node (ref "JX7") (pin "1") (pinfunction "1_1") (pintype "passive"))
      (node (ref "R4M") (pin "2") (pinfunction "2_2") (pintype "passive"))
      (node (ref "RM3") (pin "2") (pinfunction "2_2") (pintype "passive"))
    )
    (net (code "39") (name "Net-(DM2-PadA)") (class "Default")
      (node (ref "DM2") (pin "A") (pinfunction "A_A") (pintype "passive"))
      (node (ref "JX8") (pin "1") (pinfunction "1_1") (pintype "passive"))
      (node (ref "RM5") (pin "2") (pinfunction "2_2") (pintype "passive"))
      (node (ref "RM6") (pin "2") (pinfunction "2_2") (pintype "passive"))
    )
    (net (code "40") (name "Net-(IC1-~{INT})") (class "Default")
      (node (ref "IC1") (pin "1") (pinfunction "~{INT}_1") (pintype "output"))
      (node (ref "R1") (pin "1") (pinfunction "1_1") (pintype "passive"))
    )
    (net (code "41") (name "Net-(IC2A-+IN)") (class "Default")
      (node (ref "IC2") (pin "3") (pinfunction "+IN_3") (pintype "input"))
      (node (ref "RM8") (pin "2") (pinfunction "2_2") (pintype "passive"))
    )
    (net (code "42") (name "Net-(IC2A--IN)") (class "Default")
      (node (ref "DM3") (pin "C") (pinfunction "C_C") (pintype "passive"))
      (node (ref "IC2") (pin "2") (pinfunction "-IN_2") (pintype "input"))
      (node (ref "RM13") (pin "2") (pinfunction "2_2") (pintype "passive"))
    )
    (net (code "43") (name "Net-(IC2A-OUT)") (class "Default")
      (node (ref "DM3") (pin "A") (pinfunction "A_A") (pintype "passive"))
      (node (ref "IC2") (pin "1") (pinfunction "OUT_1") (pintype "output"))
      (node (ref "R15") (pin "1") (pinfunction "1_1") (pintype "passive"))
    )
    (net (code "44") (name "Net-(IC2B-+IN)") (class "Default")
      (node (ref "IC2") (pin "5") (pinfunction "+IN_5") (pintype "input"))
      (node (ref "RM7") (pin "2") (pinfunction "2_2") (pintype "passive"))
    )
    (net (code "45") (name "Net-(IC2B--IN)") (class "Default")
      (node (ref "DM4") (pin "C") (pinfunction "C_C") (pintype "passive"))
      (node (ref "IC2") (pin "6") (pinfunction "-IN_6") (pintype "input"))
      (node (ref "RM14") (pin "2") (pinfunction "2_2") (pintype "passive"))
    )
    (net (code "46") (name "Net-(IC2B-OUT)") (class "Default")
      (node (ref "DM4") (pin "A") (pinfunction "A_A") (pintype "passive"))
      (node (ref "IC2") (pin "7") (pinfunction "OUT_7") (pintype "output"))
      (node (ref "RM16") (pin "1") (pinfunction "1_1") (pintype "passive"))
    )
    (net (code "47") (name "PC4_SDA") (class "Default")
      (node (ref "IC1") (pin "23") (pinfunction "SDA_23") (pintype "bidirectional"))
      (node (ref "J3") (pin "12") (pinfunction "12_12") (pintype "passive"))
    )
    (net (code "48") (name "PC5_SCL") (class "Default")
      (node (ref "IC1") (pin "22") (pinfunction "SCL_22") (pintype "input"))
      (node (ref "J3") (pin "13") (pinfunction "13_13") (pintype "passive"))
    )
    (net (code "49") (name "RX_RF") (class "Default")
      (node (ref "C6") (pin "2") (pinfunction "2_2") (pintype "passive"))
      (node (ref "K0") (pin "3") (pinfunction "3_3") (pintype "passive"))
      (node (ref "K1") (pin "3") (pinfunction "3_3") (pintype "passive"))
      (node (ref "K2") (pin "3") (pinfunction "3_3") (pintype "passive"))
      (node (ref "K3") (pin "3") (pinfunction "3_3") (pintype "passive"))
      (node (ref "K4") (pin "3") (pinfunction "3_3") (pintype "passive"))
      (node (ref "L80") (pin "CB") (pinfunction "CB_CB") (pintype "bidirectional"))
      (node (ref "Q1") (pin "3") (pinfunction "D_3") (pintype "bidirectional"))
      (node (ref "Q2") (pin "3") (pinfunction "D_3") (pintype "bidirectional"))
      (node (ref "Q3") (pin "3") (pinfunction "D_3") (pintype "bidirectional"))
    )
    (net (code "50") (name "SWR_METER") (class "Default")
      (node (ref "JX2") (pin "1") (pinfunction "1_1") (pintype "passive"))
      (node (ref "K0") (pin "6") (pinfunction "6_6") (pintype "passive"))
      (node (ref "K1") (pin "6") (pinfunction "6_6") (pintype "passive"))
      (node (ref "K2") (pin "6") (pinfunction "6_6") (pintype "passive"))
      (node (ref "K3") (pin "6") (pinfunction "6_6") (pintype "passive"))
      (node (ref "K4") (pin "6") (pinfunction "6_6") (pintype "passive"))
    )
    (net (code "51") (name "VCC") (class "Default")
      (node (ref "C2") (pin "2") (pinfunction "2_2") (pintype "passive"))
      (node (ref "CM1") (pin "1") (pinfunction "1_1") (pintype "passive"))
      (node (ref "IC1") (pin "24") (pinfunction "VDD_24") (pintype "power_in"))
      (node (ref "IC2") (pin "8") (pinfunction "V+_8") (pintype "power_in"))
      (node (ref "J3") (pin "6") (pinfunction "6_6") (pintype "passive"))
      (node (ref "R1") (pin "2") (pinfunction "2_2") (pintype "passive"))
    )
    (net (code "52") (name "unconnected-(IC1-I{slash}O0.1-Pad5)") (class "Default")
      (node (ref "IC1") (pin "5") (pinfunction "I/O0.1_5") (pintype "bidirectional"))
    )
    (net (code "53") (name "unconnected-(IC1-I{slash}O0.2-Pad6)") (class "Default")
      (node (ref "IC1") (pin "6") (pinfunction "I/O0.2_6") (pintype "bidirectional"))
    )
    (net (code "54") (name "unconnected-(IC1-I{slash}O0.3-Pad7)") (class "Default")
      (node (ref "IC1") (pin "7") (pinfunction "I/O0.3_7") (pintype "bidirectional"))
    )
    (net (code "55") (name "unconnected-(IC1-I{slash}O0.4-Pad8)") (class "Default")
      (node (ref "IC1") (pin "8") (pinfunction "I/O0.4_8") (pintype "bidirectional"))
    )
    (net (code "56") (name "unconnected-(IC1-I{slash}O0.5-Pad9)") (class "Default")
      (node (ref "IC1") (pin "9") (pinfunction "I/O0.5_9") (pintype "bidirectional"))
    )
    (net (code "57") (name "unconnected-(IC1-I{slash}O0.6-Pad10)") (class "Default")
      (node (ref "IC1") (pin "10") (pinfunction "I/O0.6_10") (pintype "bidirectional"))
    )
    (net (code "58") (name "unconnected-(IC1-I{slash}O0.7-Pad11)") (class "Default")
      (node (ref "IC1") (pin "11") (pinfunction "I/O0.7_11") (pintype "bidirectional"))
    )
    (net (code "59") (name "unconnected-(IC1-I{slash}O1.0-Pad13)") (class "Default")
      (node (ref "IC1") (pin "13") (pinfunction "I/O1.0_13") (pintype "bidirectional"))
    )
    (net (code "60") (name "unconnected-(IC1-I{slash}O1.2-Pad15)") (class "Default")
      (node (ref "IC1") (pin "15") (pinfunction "I/O1.2_15") (pintype "bidirectional"))
    )
    (net (code "61") (name "unconnected-(IC1-I{slash}O1.7-Pad20)") (class "Default")
      (node (ref "IC1") (pin "20") (pinfunction "I/O1.7_20") (pintype "bidirectional"))
    )
    (net (code "62") (name "unconnected-(J3-Pad2)") (class "Default")
      (node (ref "J3") (pin "2") (pinfunction "2_2") (pintype "passive"))
    )
    (net (code "63") (name "unconnected-(J3-Pad3)") (class "Default")
      (node (ref "J3") (pin "3") (pinfunction "3_3") (pintype "passive"))
    )
    (net (code "64") (name "unconnected-(J3-Pad4)") (class "Default")
      (node (ref "J3") (pin "4") (pinfunction "4_4") (pintype "passive"))
    )
    (net (code "65") (name "unconnected-(J3-Pad5)") (class "Default")
      (node (ref "J3") (pin "5") (pinfunction "5_5") (pintype "passive"))
    )
    (net (code "66") (name "unconnected-(J3-Pad8)") (class "Default")
      (node (ref "J3") (pin "8") (pinfunction "8_8") (pintype "passive"))
    )
    (net (code "67") (name "unconnected-(J3-Pad9)") (class "Default")
      (node (ref "J3") (pin "9") (pinfunction "9_9") (pintype "passive"))
    )
    (net (code "68") (name "unconnected-(J3-Pad10)") (class "Default")
      (node (ref "J3") (pin "10") (pinfunction "10_10") (pintype "passive"))
    )
    (net (code "69") (name "unconnected-(J3-Pad11)") (class "Default")
      (node (ref "J3") (pin "11") (pinfunction "11_11") (pintype "passive"))
    )
    (net (code "70") (name "unconnected-(J9-Pad2)") (class "Default")
      (node (ref "J9") (pin "2") (pinfunction "2_2") (pintype "passive"))
    )
    (net (code "71") (name "unconnected-(J9-Pad3)") (class "Default")
      (node (ref "J9") (pin "3") (pinfunction "3_3") (pintype "passive"))
    )
    (net (code "72") (name "unconnected-(J9-Pad4)") (class "Default")
      (node (ref "J9") (pin "4") (pinfunction "4_4") (pintype "passive"))
    )
    (net (code "73") (name "unconnected-(J9-Pad5)") (class "Default")
      (node (ref "J9") (pin "5") (pinfunction "5_5") (pintype "passive"))
    )
    (net (code "74") (name "unconnected-(J9-Pad6)") (class "Default")
      (node (ref "J9") (pin "6") (pinfunction "6_6") (pintype "passive"))
    )
    (net (code "75") (name "unconnected-(J9-Pad9)") (class "Default")
      (node (ref "J9") (pin "9") (pinfunction "9_9") (pintype "passive"))
    )
    (net (code "76") (name "unconnected-(J9-Pad10)") (class "Default")
      (node (ref "J9") (pin "10") (pinfunction "10_10") (pintype "passive"))
    )
    (net (code "77") (name "unconnected-(J9-Pad11)") (class "Default")
      (node (ref "J9") (pin "11") (pinfunction "11_11") (pintype "passive"))
    )
    (net (code "78") (name "unconnected-(J9-Pad12)") (class "Default")
      (node (ref "J9") (pin "12") (pinfunction "12_12") (pintype "passive"))
    )
    (net (code "79") (name "unconnected-(K0-Pad2)") (class "Default")
      (node (ref "K0") (pin "2") (pinfunction "2_2") (pintype "passive"))
    )
    (net (code "80") (name "unconnected-(K0-Pad7)") (class "Default")
      (node (ref "K0") (pin "7") (pinfunction "7_7") (pintype "passive"))
    )
    (net (code "81") (name "unconnected-(K1-Pad2)") (class "Default")
      (node (ref "K1") (pin "2") (pinfunction "2_2") (pintype "passive"))
    )
    (net (code "82") (name "unconnected-(K1-Pad7)") (class "Default")
      (node (ref "K1") (pin "7") (pinfunction "7_7") (pintype "passive"))
    )
    (net (code "83") (name "unconnected-(K2-Pad2)") (class "Default")
      (node (ref "K2") (pin "2") (pinfunction "2_2") (pintype "passive"))
    )
    (net (code "84") (name "unconnected-(K2-Pad7)") (class "Default")
      (node (ref "K2") (pin "7") (pinfunction "7_7") (pintype "passive"))
    )
    (net (code "85") (name "unconnected-(K3-Pad2)") (class "Default")
      (node (ref "K3") (pin "2") (pinfunction "2_2") (pintype "passive"))
    )
    (net (code "86") (name "unconnected-(K3-Pad7)") (class "Default")
      (node (ref "K3") (pin "7") (pinfunction "7_7") (pintype "passive"))
    )
    (net (code "87") (name "unconnected-(K4-Pad2)") (class "Default")
      (node (ref "K4") (pin "2") (pinfunction "2_2") (pintype "passive"))
    )
    (net (code "88") (name "unconnected-(K4-Pad7)") (class "Default")
      (node (ref "K4") (pin "7") (pinfunction "7_7") (pintype "passive"))
    )
  )
)
